# CAN.net
KiCad netlist of a schematic drawn in Altium Designer
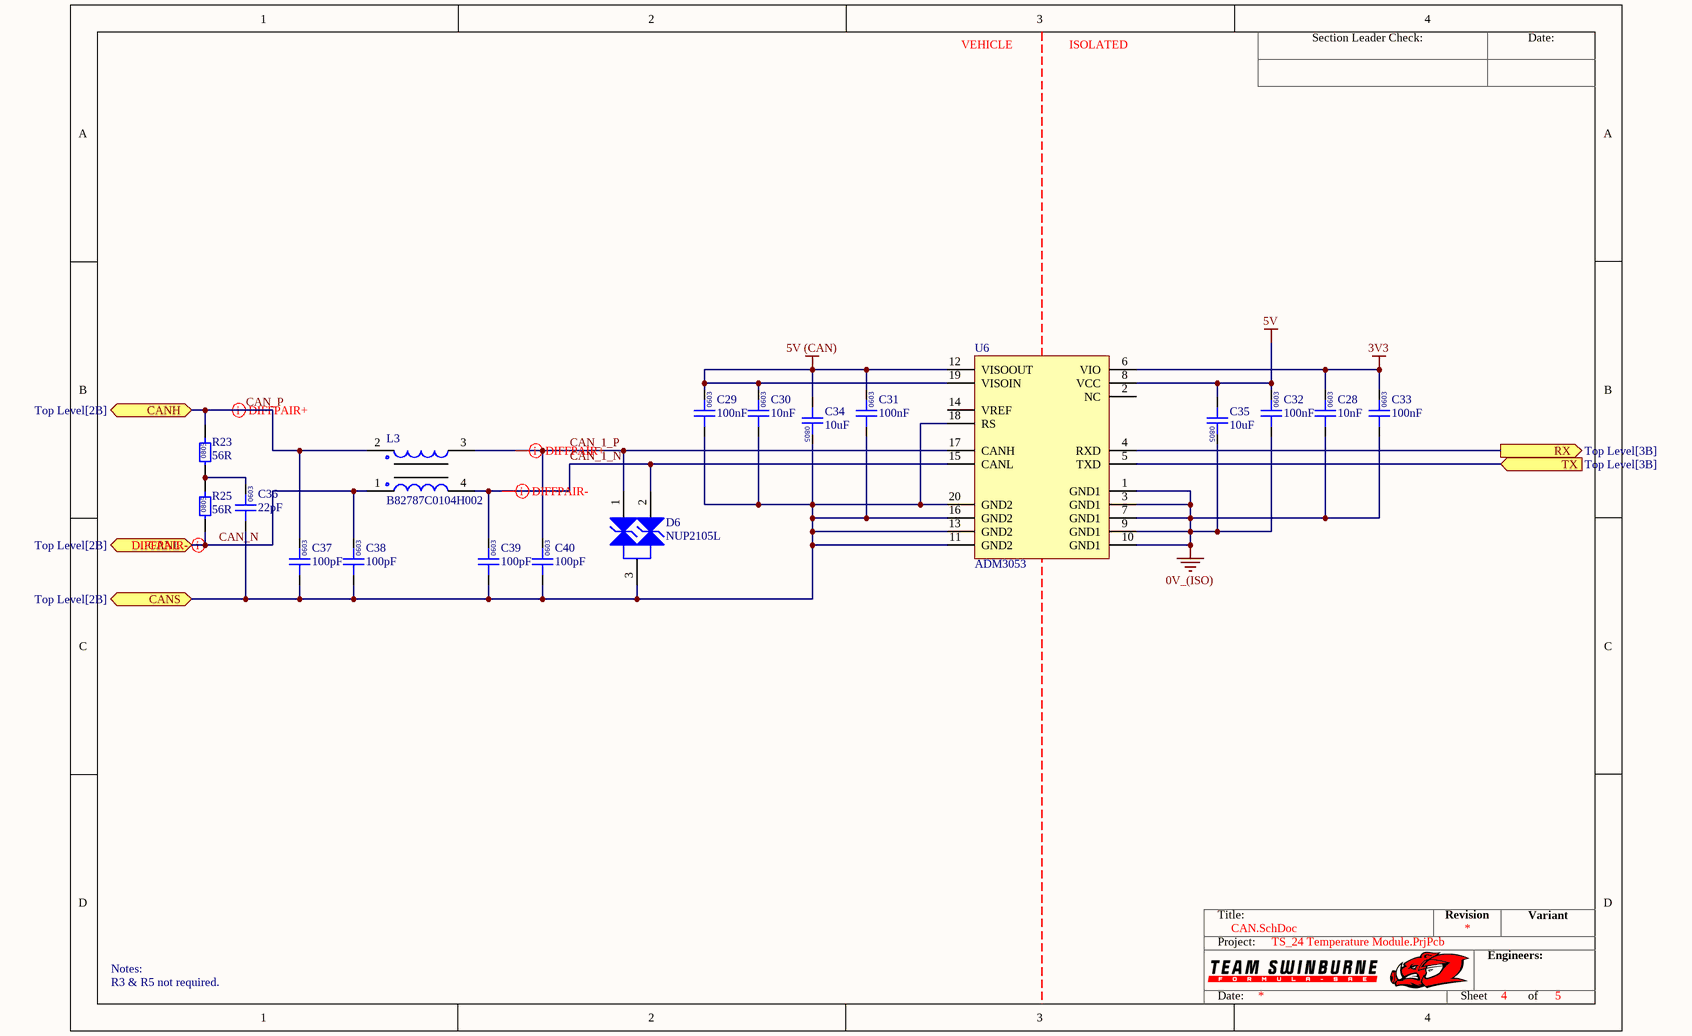
[diagram p0: CAN.SchDoc]

(export (version "E")
  (design (tool "Eeschema 10.0.6"))
  (components
    (comp (ref "C28")
      (value "10nF")
      (footprint "0603")
      (fields
        (field (name "PART NUMBER") "GCM188L81H103KA03D")
        (field (name "MANUFACTURER") "muRata")
        (field (name "TOLERANCE") "±10%")
      )
      (libsource (lib "ts_standard_library") (part "Capacitor 0603"))
    )
    (comp (ref "C29")
      (value "100nF")
      (footprint "0603")
      (fields
        (field (name "PART NUMBER") "GCM188L81H104KA57D")
        (field (name "MANUFACTURER") "muRata")
        (field (name "TOLERANCE") "±10%")
      )
      (libsource (lib "ts_standard_library") (part "Capacitor 0603"))
    )
    (comp (ref "C30")
      (value "10nF")
      (footprint "0603")
      (fields
        (field (name "PART NUMBER") "GCM188L81H103KA03D")
        (field (name "MANUFACTURER") "muRata")
        (field (name "TOLERANCE") "±10%")
      )
      (libsource (lib "ts_standard_library") (part "Capacitor 0603"))
    )
    (comp (ref "C31")
      (value "100nF")
      (footprint "0603")
      (fields
        (field (name "PART NUMBER") "GCM188L81H104KA57D")
        (field (name "MANUFACTURER") "muRata")
        (field (name "TOLERANCE") "±10%")
      )
      (libsource (lib "ts_standard_library") (part "Capacitor 0603"))
    )
    (comp (ref "C32")
      (value "100nF")
      (footprint "0603")
      (fields
        (field (name "PART NUMBER") "GCM188L81H104KA57D")
        (field (name "MANUFACTURER") "muRata")
        (field (name "TOLERANCE") "±10%")
      )
      (libsource (lib "ts_standard_library") (part "Capacitor 0603"))
    )
    (comp (ref "C33")
      (value "100nF")
      (footprint "0603")
      (fields
        (field (name "PART NUMBER") "GCM188L81H104KA57D")
        (field (name "MANUFACTURER") "muRata")
        (field (name "TOLERANCE") "±10%")
      )
      (libsource (lib "ts_standard_library") (part "Capacitor 0603"))
    )
    (comp (ref "C34")
      (value "10uF")
      (footprint "0805")
      (fields
        (field (name "PART NUMBER") "GRM21BR6YA106KE43L")
        (field (name "MANUFACTURER") "muRata")
        (field (name "TOLERANCE") "10%")
      )
      (libsource (lib "ts_standard_library") (part "Capacitor 0805"))
    )
    (comp (ref "C35")
      (value "10uF")
      (footprint "0805")
      (fields
        (field (name "PART NUMBER") "GRM21BR6YA106KE43L")
        (field (name "MANUFACTURER") "muRata")
        (field (name "TOLERANCE") "10%")
      )
      (libsource (lib "ts_standard_library") (part "Capacitor 0805"))
    )
    (comp (ref "C36")
      (value "22pF")
      (footprint "0603")
      (fields
        (field (name "PART NUMBER") "GRM0335C1H220JA01D")
        (field (name "MANUFACTURER") "Murata Electronics")
        (field (name "TOLERANCE") "±5%")
      )
      (libsource (lib "ts_standard_library") (part "Capacitor 0603"))
    )
    (comp (ref "C37")
      (value "100pF")
      (footprint "0603")
      (fields
        (field (name "PART NUMBER") "GRM1885C1H101JA01D")
        (field (name "MANUFACTURER") "Murata Electronics")
        (field (name "TOLERANCE") "±5%")
      )
      (libsource (lib "ts_standard_library") (part "Capacitor 0603"))
    )
    (comp (ref "C38")
      (value "100pF")
      (footprint "0603")
      (fields
        (field (name "PART NUMBER") "GRM1885C1H101JA01D")
        (field (name "MANUFACTURER") "Murata Electronics")
        (field (name "TOLERANCE") "±5%")
      )
      (libsource (lib "ts_standard_library") (part "Capacitor 0603"))
    )
    (comp (ref "C39")
      (value "100pF")
      (footprint "0603")
      (fields
        (field (name "PART NUMBER") "GRM1885C1H101JA01D")
        (field (name "MANUFACTURER") "Murata Electronics")
        (field (name "TOLERANCE") "±5%")
      )
      (libsource (lib "ts_standard_library") (part "Capacitor 0603"))
    )
    (comp (ref "C40")
      (value "100pF")
      (footprint "0603")
      (fields
        (field (name "PART NUMBER") "GRM1885C1H101JA01D")
        (field (name "MANUFACTURER") "Murata Electronics")
        (field (name "TOLERANCE") "±5%")
      )
      (libsource (lib "ts_standard_library") (part "Capacitor 0603"))
    )
    (comp (ref "D6")
      (value "NUP2105L")
      (footprint "ONSC-SOT-23-3-318-08_V")
      (description "NUP2105L Series 350 W Dual Line CAN Bus Protector ESD Protection Diode - SOT-23")
      (libsource (lib "Team Swinburne") (part "ONSC-NUP21X5X-SOT-23-3-318-08"))
    )
    (comp (ref "L3")
      (value "B82787C0104H002")
      (footprint "TDK 4-PC Pad")
      (fields
        (field (name "MANUFACTURER") "EPCOS (TDK)")
        (field (name "DIGIKEY PART NUMBER") "495-4598-1-ND")
      )
      (libsource (lib "ts_standard_library") (part "B82787C0104H002"))
    )
    (comp (ref "R23")
      (value "56R")
      (footprint "0805")
      (fields
        (field (name "PART NUMBER") "RC0805FR0756RL")
        (field (name "MANUFACTURER") "YAGEO")
        (field (name "TOLERANCE") "0.01")
      )
      (libsource (lib "ts_standard_library") (part "Resistor 0805"))
    )
    (comp (ref "R25")
      (value "56R")
      (footprint "0805")
      (fields
        (field (name "PART NUMBER") "RC0805FR0756RL")
        (field (name "MANUFACTURER") "YAGEO")
        (field (name "TOLERANCE") "0.01")
      )
      (libsource (lib "ts_standard_library") (part "Resistor 0805"))
    )
    (comp (ref "U6")
      (value "ADM3053")
      (footprint "AD SOIC-W 20")
      (description "Isolated CAN Transceiver")
      (fields
        (field (name "MANUFACTURER") "Analogue Devices")
        (field (name "DIGIKEY PART NUMBER") "ADM3053BRWZ-ND")
      )
      (libsource (lib "ts_standard_library") (part "ADM3053"))
    )
  )
  (nets
    (net (code "1") (name "/CANS") (class "Default")
      (node (ref "C29") (pin "1") (pinfunction "1_1") (pintype "passive"))
      (node (ref "C30") (pin "1") (pinfunction "1_1") (pintype "passive"))
      (node (ref "C31") (pin "1") (pinfunction "1_1") (pintype "passive"))
      (node (ref "C34") (pin "2") (pinfunction "2_2") (pintype "passive"))
      (node (ref "C36") (pin "1") (pinfunction "1_1") (pintype "passive"))
      (node (ref "C37") (pin "1") (pinfunction "1_1") (pintype "passive"))
      (node (ref "C38") (pin "1") (pinfunction "1_1") (pintype "passive"))
      (node (ref "C39") (pin "1") (pinfunction "1_1") (pintype "passive"))
      (node (ref "C40") (pin "1") (pinfunction "1_1") (pintype "passive"))
      (node (ref "D6") (pin "3") (pinfunction "K_3") (pintype "passive"))
      (node (ref "U6") (pin "11") (pinfunction "GND2_11") (pintype "passive"))
      (node (ref "U6") (pin "13") (pinfunction "GND2_13") (pintype "passive"))
      (node (ref "U6") (pin "16") (pinfunction "GND2_16") (pintype "passive"))
      (node (ref "U6") (pin "18") (pinfunction "RS_18") (pintype "passive"))
      (node (ref "U6") (pin "20") (pinfunction "GND2_20") (pintype "passive"))
    )
    (net (code "2") (name "/CAN_1_N") (class "Default")
      (node (ref "C39") (pin "2") (pinfunction "2_2") (pintype "passive"))
      (node (ref "D6") (pin "2") (pinfunction "K_2") (pintype "passive"))
      (node (ref "L3") (pin "4") (pinfunction "4_4") (pintype "passive"))
      (node (ref "U6") (pin "15") (pinfunction "CANL_15") (pintype "passive"))
    )
    (net (code "3") (name "/CAN_1_P") (class "Default")
      (node (ref "C40") (pin "2") (pinfunction "2_2") (pintype "passive"))
      (node (ref "D6") (pin "1") (pinfunction "K_1") (pintype "passive"))
      (node (ref "L3") (pin "3") (pinfunction "3_3") (pintype "passive"))
      (node (ref "U6") (pin "17") (pinfunction "CANH_17") (pintype "passive"))
    )
    (net (code "4") (name "/CAN_N") (class "Default")
      (node (ref "C38") (pin "2") (pinfunction "2_2") (pintype "passive"))
      (node (ref "L3") (pin "1") (pinfunction "1_1") (pintype "passive"))
      (node (ref "R25") (pin "1") (pinfunction "1_1") (pintype "passive"))
    )
    (net (code "5") (name "/CAN_P") (class "Default")
      (node (ref "C37") (pin "2") (pinfunction "2_2") (pintype "passive"))
      (node (ref "L3") (pin "2") (pinfunction "2_2") (pintype "passive"))
      (node (ref "R23") (pin "2") (pinfunction "2_2") (pintype "passive"))
    )
    (net (code "6") (name "/RX") (class "Default")
      (node (ref "U6") (pin "4") (pinfunction "RXD_4") (pintype "passive"))
    )
    (net (code "7") (name "/TX") (class "Default")
      (node (ref "U6") (pin "5") (pinfunction "TXD_5") (pintype "passive"))
    )
    (net (code "8") (name "0V_(ISO)") (class "Default")
      (node (ref "C28") (pin "1") (pinfunction "1_1") (pintype "passive"))
      (node (ref "C32") (pin "1") (pinfunction "1_1") (pintype "passive"))
      (node (ref "C33") (pin "1") (pinfunction "1_1") (pintype "passive"))
      (node (ref "C35") (pin "2") (pinfunction "2_2") (pintype "passive"))
      (node (ref "U6") (pin "1") (pinfunction "GND1_1") (pintype "passive"))
      (node (ref "U6") (pin "10") (pinfunction "GND1_10") (pintype "passive"))
      (node (ref "U6") (pin "3") (pinfunction "GND1_3") (pintype "passive"))
      (node (ref "U6") (pin "7") (pinfunction "GND1_7") (pintype "passive"))
      (node (ref "U6") (pin "9") (pinfunction "GND1_9") (pintype "passive"))
    )
    (net (code "9") (name "3V3") (class "Default")
      (node (ref "C28") (pin "2") (pinfunction "2_2") (pintype "passive"))
      (node (ref "C33") (pin "2") (pinfunction "2_2") (pintype "passive"))
      (node (ref "U6") (pin "6") (pinfunction "VIO_6") (pintype "passive"))
    )
    (net (code "10") (name "5V") (class "Default")
      (node (ref "C32") (pin "2") (pinfunction "2_2") (pintype "passive"))
      (node (ref "C35") (pin "1") (pinfunction "1_1") (pintype "passive"))
      (node (ref "U6") (pin "8") (pinfunction "VCC_8") (pintype "passive"))
    )
    (net (code "11") (name "5V (CAN)") (class "Default")
      (node (ref "C29") (pin "2") (pinfunction "2_2") (pintype "passive"))
      (node (ref "C30") (pin "2") (pinfunction "2_2") (pintype "passive"))
      (node (ref "C31") (pin "2") (pinfunction "2_2") (pintype "passive"))
      (node (ref "C34") (pin "1") (pinfunction "1_1") (pintype "passive"))
      (node (ref "U6") (pin "12") (pinfunction "VISOOUT_12") (pintype "passive"))
      (node (ref "U6") (pin "19") (pinfunction "VISOIN_19") (pintype "passive"))
    )
    (net (code "12") (name "Net-(C36-Pad2)") (class "Default")
      (node (ref "C36") (pin "2") (pinfunction "2_2") (pintype "passive"))
      (node (ref "R23") (pin "1") (pinfunction "1_1") (pintype "passive"))
      (node (ref "R25") (pin "2") (pinfunction "2_2") (pintype "passive"))
    )
    (net (code "13") (name "unconnected-(U6-NC-Pad2)") (class "Default")
      (node (ref "U6") (pin "2") (pinfunction "NC_2") (pintype "passive"))
    )
    (net (code "14") (name "unconnected-(U6-VREF-Pad14)") (class "Default")
      (node (ref "U6") (pin "14") (pinfunction "VREF_14") (pintype "passive"))
    )
  )
)
